# Audio_Power_Supply.net
KiCad netlist of a schematic drawn in Altium Designer
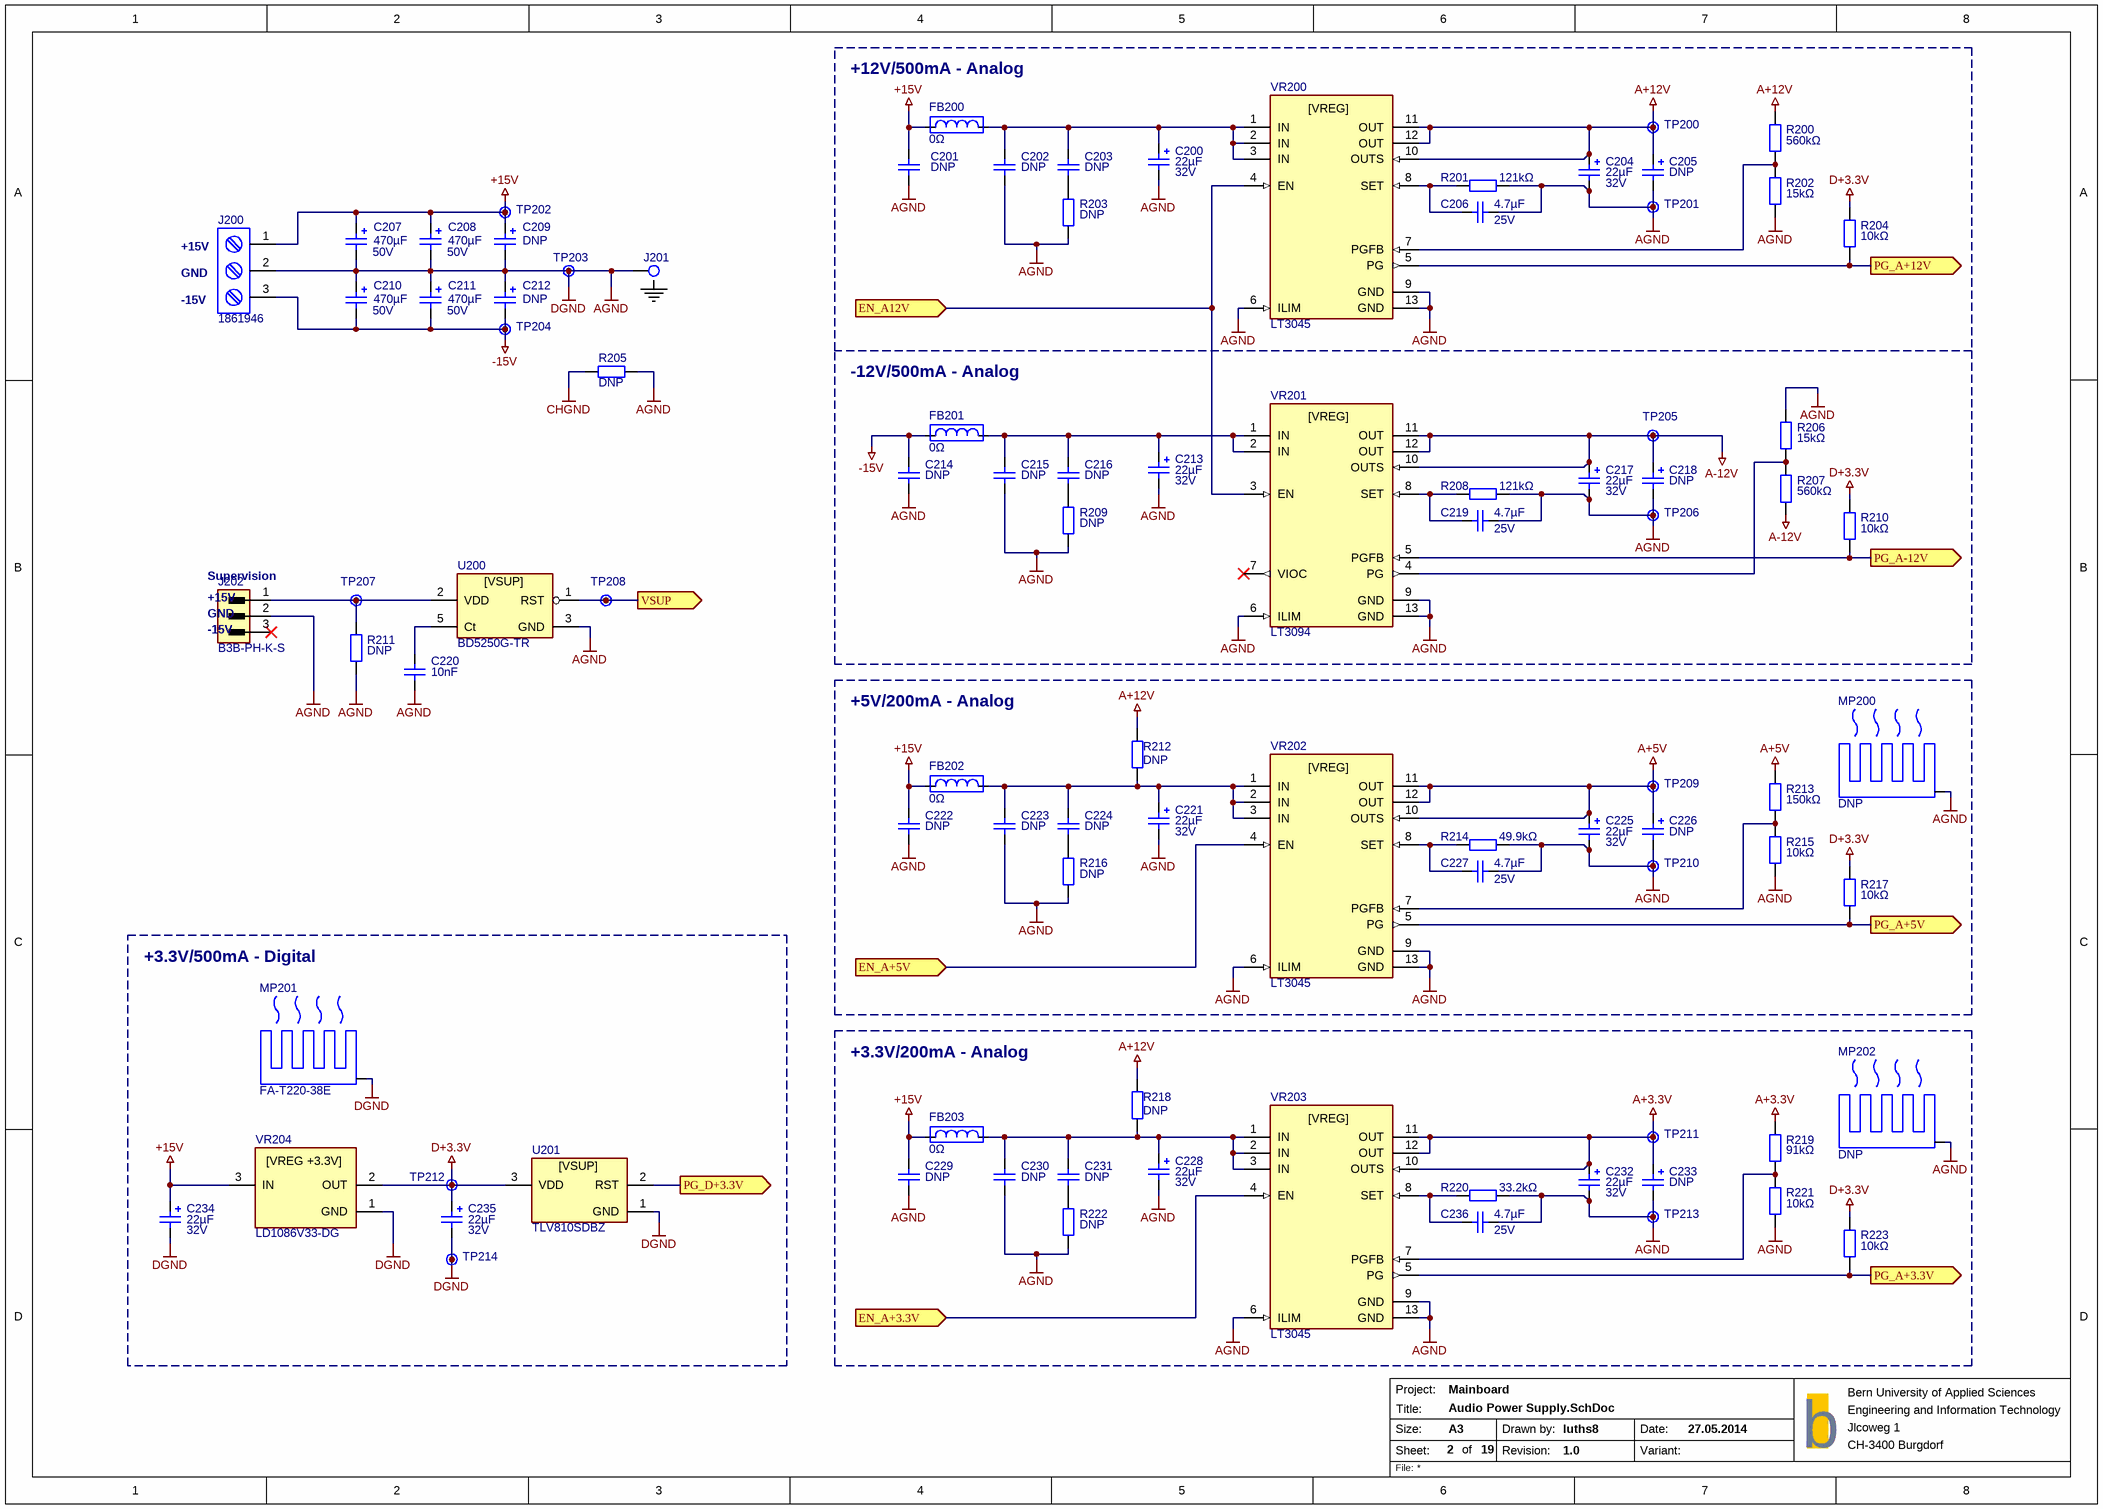
[diagram p0: Audio Power Supply.SchDoc]

(export (version "E")
  (design (tool "Eeschema 10.0.6"))
  (components
    (comp (ref "C200")
      (value "22µF")
      (footprint "CAP-6.3-5.5-2.5")
      (description "Elektrolytic Capacitor")
      (fields (field (name "VOLTAGE") "32V") (field (name "MANUFACTURER PART NO.") "32SEPF22M"))
      (libsource (lib "Audio-Streamer") (part "Capacitor Electrolytic"))
    )
    (comp (ref "C201")
      (value "DNP")
      (footprint "SMD0805CAP")
      (description "Ceramic Capacitor")
      (fields (field (name "VOLTAGE") "25V"))
      (libsource (lib "Audio-Streamer") (part "Capacitor Ceramic"))
    )
    (comp (ref "C202")
      (value "DNP")
      (footprint "SMD0805CAP")
      (description "Ceramic Capacitor")
      (fields (field (name "VOLTAGE") "25V"))
      (libsource (lib "Audio-Streamer") (part "Capacitor Ceramic"))
    )
    (comp (ref "C203")
      (value "DNP")
      (footprint "SMD0805CAP")
      (description "Ceramic Capacitor")
      (fields (field (name "VOLTAGE") "25V"))
      (libsource (lib "Audio-Streamer") (part "Capacitor Ceramic"))
    )
    (comp (ref "C204")
      (value "22µF")
      (footprint "CAP-6.3-5.5-2.5")
      (description "Elektrolytic Capacitor")
      (fields (field (name "VOLTAGE") "32V") (field (name "MANUFACTURER PART NO.") "32SEPF22M"))
      (libsource (lib "Audio-Streamer") (part "Capacitor Electrolytic"))
    )
    (comp (ref "C205")
      (value "DNP")
      (footprint "CAP-6.3-5.5-2.5")
      (description "Elektrolytic Capacitor")
      (fields (field (name "VOLTAGE") "32V") (field (name "MANUFACTURER PART NO.") "32SEPF22M"))
      (libsource (lib "Audio-Streamer") (part "Capacitor Electrolytic"))
    )
    (comp (ref "C206")
      (value "4.7µF")
      (footprint "SMD1206CAP")
      (description "Ceramic Capacitor")
      (fields (field (name "VOLTAGE") "25V"))
      (libsource (lib "Audio-Streamer") (part "Capacitor Ceramic"))
    )
    (comp (ref "C207")
      (value "470µF")
      (footprint "CAP-12.5-20-5")
      (description "Elektrolytic Capacitor")
      (fields (field (name "VOLTAGE") "50V") (field (name "MANUFACTURER PART NO.") "EEU-FR1H471"))
      (libsource (lib "Audio-Streamer") (part "Capacitor Electrolytic"))
    )
    (comp (ref "C208")
      (value "470µF")
      (footprint "CAP-12.5-20-5")
      (description "Elektrolytic Capacitor")
      (fields (field (name "VOLTAGE") "50V") (field (name "MANUFACTURER PART NO.") "EEU-FR1H471"))
      (libsource (lib "Audio-Streamer") (part "Capacitor Electrolytic"))
    )
    (comp (ref "C209")
      (value "DNP")
      (footprint "CAP-12.5-20-5")
      (description "Elektrolytic Capacitor")
      (fields (field (name "VOLTAGE") "50V") (field (name "MANUFACTURER PART NO.") "EEU-FR1H471"))
      (libsource (lib "Audio-Streamer") (part "Capacitor Electrolytic"))
    )
    (comp (ref "C210")
      (value "470µF")
      (footprint "CAP-12.5-20-5")
      (description "Elektrolytic Capacitor")
      (fields (field (name "VOLTAGE") "50V") (field (name "MANUFACTURER PART NO.") "EEU-FR1H471"))
      (libsource (lib "Audio-Streamer") (part "Capacitor Electrolytic"))
    )
    (comp (ref "C211")
      (value "470µF")
      (footprint "CAP-12.5-20-5")
      (description "Elektrolytic Capacitor")
      (fields (field (name "VOLTAGE") "50V") (field (name "MANUFACTURER PART NO.") "EEU-FR1H471"))
      (libsource (lib "Audio-Streamer") (part "Capacitor Electrolytic"))
    )
    (comp (ref "C212")
      (value "DNP")
      (footprint "CAP-12.5-20-5")
      (description "Elektrolytic Capacitor")
      (fields (field (name "VOLTAGE") "50V") (field (name "MANUFACTURER PART NO.") "EEU-FR1H471"))
      (libsource (lib "Audio-Streamer") (part "Capacitor Electrolytic"))
    )
    (comp (ref "C213")
      (value "22µF")
      (footprint "CAP-6.3-5.5-2.5")
      (description "Elektrolytic Capacitor")
      (fields (field (name "VOLTAGE") "32V") (field (name "MANUFACTURER PART NO.") "32SEPF22M"))
      (libsource (lib "Audio-Streamer") (part "Capacitor Electrolytic"))
    )
    (comp (ref "C214")
      (value "DNP")
      (footprint "SMD0805CAP")
      (description "Ceramic Capacitor")
      (fields (field (name "VOLTAGE") "25V"))
      (libsource (lib "Audio-Streamer") (part "Capacitor Ceramic"))
    )
    (comp (ref "C215")
      (value "DNP")
      (footprint "SMD0805CAP")
      (description "Ceramic Capacitor")
      (fields (field (name "VOLTAGE") "25V"))
      (libsource (lib "Audio-Streamer") (part "Capacitor Ceramic"))
    )
    (comp (ref "C216")
      (value "DNP")
      (footprint "SMD0805CAP")
      (description "Ceramic Capacitor")
      (fields (field (name "VOLTAGE") "25V"))
      (libsource (lib "Audio-Streamer") (part "Capacitor Ceramic"))
    )
    (comp (ref "C217")
      (value "22µF")
      (footprint "CAP-6.3-5.5-2.5")
      (description "Elektrolytic Capacitor")
      (fields (field (name "VOLTAGE") "32V") (field (name "MANUFACTURER PART NO.") "32SEPF22M"))
      (libsource (lib "Audio-Streamer") (part "Capacitor Electrolytic"))
    )
    (comp (ref "C218")
      (value "DNP")
      (footprint "CAP-6.3-5.5-2.5")
      (description "Elektrolytic Capacitor")
      (fields (field (name "VOLTAGE") "32V") (field (name "MANUFACTURER PART NO.") "32SEPF22M"))
      (libsource (lib "Audio-Streamer") (part "Capacitor Electrolytic"))
    )
    (comp (ref "C219")
      (value "4.7µF")
      (footprint "SMD1206CAP")
      (description "Ceramic Capacitor")
      (fields (field (name "VOLTAGE") "25V"))
      (libsource (lib "Audio-Streamer") (part "Capacitor Ceramic"))
    )
    (comp (ref "C220")
      (value "10nF")
      (footprint "SMD0603CAP")
      (description "Ceramic Capacitor")
      (fields (field (name "VOLTAGE") "25V"))
      (libsource (lib "Audio-Streamer") (part "Capacitor Ceramic"))
    )
    (comp (ref "C221")
      (value "22µF")
      (footprint "CAP-6.3-5.5-2.5")
      (description "Elektrolytic Capacitor")
      (fields (field (name "VOLTAGE") "32V") (field (name "MANUFACTURER PART NO.") "32SEPF22M"))
      (libsource (lib "Audio-Streamer") (part "Capacitor Electrolytic"))
    )
    (comp (ref "C222")
      (value "DNP")
      (footprint "SMD0805CAP")
      (description "Ceramic Capacitor")
      (fields (field (name "VOLTAGE") "25V"))
      (libsource (lib "Audio-Streamer") (part "Capacitor Ceramic"))
    )
    (comp (ref "C223")
      (value "DNP")
      (footprint "SMD0805CAP")
      (description "Ceramic Capacitor")
      (fields (field (name "VOLTAGE") "25V"))
      (libsource (lib "Audio-Streamer") (part "Capacitor Ceramic"))
    )
    (comp (ref "C224")
      (value "DNP")
      (footprint "SMD0805CAP")
      (description "Ceramic Capacitor")
      (fields (field (name "VOLTAGE") "25V"))
      (libsource (lib "Audio-Streamer") (part "Capacitor Ceramic"))
    )
    (comp (ref "C225")
      (value "22µF")
      (footprint "CAP-6.3-5.5-2.5")
      (description "Elektrolytic Capacitor")
      (fields (field (name "VOLTAGE") "32V") (field (name "MANUFACTURER PART NO.") "32SEPF22M"))
      (libsource (lib "Audio-Streamer") (part "Capacitor Electrolytic"))
    )
    (comp (ref "C226")
      (value "DNP")
      (footprint "CAP-6.3-5.5-2.5")
      (description "Elektrolytic Capacitor")
      (fields (field (name "VOLTAGE") "32V") (field (name "MANUFACTURER PART NO.") "32SEPF22M"))
      (libsource (lib "Audio-Streamer") (part "Capacitor Electrolytic"))
    )
    (comp (ref "C227")
      (value "4.7µF")
      (footprint "SMD1206CAP")
      (description "Ceramic Capacitor")
      (fields (field (name "VOLTAGE") "25V"))
      (libsource (lib "Audio-Streamer") (part "Capacitor Ceramic"))
    )
    (comp (ref "C228")
      (value "22µF")
      (footprint "CAP-6.3-5.5-2.5")
      (description "Elektrolytic Capacitor")
      (fields (field (name "VOLTAGE") "32V") (field (name "MANUFACTURER PART NO.") "32SEPF22M"))
      (libsource (lib "Audio-Streamer") (part "Capacitor Electrolytic"))
    )
    (comp (ref "C229")
      (value "DNP")
      (footprint "SMD0805CAP")
      (description "Ceramic Capacitor")
      (fields (field (name "VOLTAGE") "25V"))
      (libsource (lib "Audio-Streamer") (part "Capacitor Ceramic"))
    )
    (comp (ref "C230")
      (value "DNP")
      (footprint "SMD0805CAP")
      (description "Ceramic Capacitor")
      (fields (field (name "VOLTAGE") "25V"))
      (libsource (lib "Audio-Streamer") (part "Capacitor Ceramic"))
    )
    (comp (ref "C231")
      (value "DNP")
      (footprint "SMD0805CAP")
      (description "Ceramic Capacitor")
      (fields (field (name "VOLTAGE") "25V"))
      (libsource (lib "Audio-Streamer") (part "Capacitor Ceramic"))
    )
    (comp (ref "C232")
      (value "22µF")
      (footprint "CAP-6.3-5.5-2.5")
      (description "Elektrolytic Capacitor")
      (fields (field (name "VOLTAGE") "32V") (field (name "MANUFACTURER PART NO.") "32SEPF22M"))
      (libsource (lib "Audio-Streamer") (part "Capacitor Electrolytic"))
    )
    (comp (ref "C233")
      (value "DNP")
      (footprint "CAP-6.3-5.5-2.5")
      (description "Elektrolytic Capacitor")
      (fields (field (name "VOLTAGE") "32V") (field (name "MANUFACTURER PART NO.") "32SEPF22M"))
      (libsource (lib "Audio-Streamer") (part "Capacitor Electrolytic"))
    )
    (comp (ref "C234")
      (value "22µF")
      (footprint "CAP-6.3-5.5-2.5")
      (description "Elektrolytic Capacitor")
      (fields (field (name "VOLTAGE") "32V") (field (name "MANUFACTURER PART NO.") "32SEPF22M"))
      (libsource (lib "Audio-Streamer") (part "Capacitor Electrolytic"))
    )
    (comp (ref "C235")
      (value "22µF")
      (footprint "CAP-6.3-5.5-2.5")
      (description "Elektrolytic Capacitor")
      (fields (field (name "VOLTAGE") "32V") (field (name "MANUFACTURER PART NO.") "32SEPF22M"))
      (libsource (lib "Audio-Streamer") (part "Capacitor Electrolytic"))
    )
    (comp (ref "C236")
      (value "4.7µF")
      (footprint "SMD1206CAP")
      (description "Ceramic Capacitor")
      (fields (field (name "VOLTAGE") "25V"))
      (libsource (lib "Audio-Streamer") (part "Capacitor Ceramic"))
    )
    (comp (ref "FB200")
      (value "0Ω")
      (footprint "SMD0603RES")
      (description "Ferrite Bead")
      (libsource (lib "Audio-Streamer") (part "Ferrite Bead"))
    )
    (comp (ref "FB201")
      (value "0Ω")
      (footprint "SMD0603RES")
      (description "Ferrite Bead")
      (libsource (lib "Audio-Streamer") (part "Ferrite Bead"))
    )
    (comp (ref "FB202")
      (value "0Ω")
      (footprint "SMD0603RES")
      (description "Ferrite Bead")
      (libsource (lib "Audio-Streamer") (part "Ferrite Bead"))
    )
    (comp (ref "FB203")
      (value "0Ω")
      (footprint "SMD0603RES")
      (description "Ferrite Bead")
      (libsource (lib "Audio-Streamer") (part "Ferrite Bead"))
    )
    (comp (ref "J200")
      (value "1861946")
      (footprint "1861946")
      (description "Screw Terminal, 3 Position")
      (libsource (lib "Audio-Streamer") (part "1861946"))
    )
    (comp (ref "J201")
      (value "Solder Pin")
      (footprint "SOLDER_PIN")
      (libsource (lib "Audio-Streamer") (part "Solder Pin"))
    )
    (comp (ref "J202")
      (value "B3B-PH-K-S")
      (footprint "B3B-PH-K-S")
      (description "Connector 3x1P")
      (libsource (lib "Audio-Streamer") (part "Connector 3x1P"))
    )
    (comp (ref "MP200")
      (value "DNP")
      (footprint "DA-T263-201E")
      (description "Heatsink")
      (fields (field (name "MANUFACTURER PART NO.") "DA-T263-201E"))
      (libsource (lib "Audio-Streamer") (part "Heatsink"))
    )
    (comp (ref "MP201")
      (value "FA-T220-38E")
      (footprint "FA-T220-38E")
      (description "Heatsink")
      (libsource (lib "Audio-Streamer") (part "Heatsink"))
    )
    (comp (ref "MP202")
      (value "DNP")
      (footprint "DA-T263-201E")
      (description "Heatsink")
      (fields (field (name "MANUFACTURER PART NO.") "DA-T263-201E"))
      (libsource (lib "Audio-Streamer") (part "Heatsink"))
    )
    (comp (ref "R200")
      (value "560kΩ")
      (footprint "SMD0603RES")
      (description "Resistor")
      (libsource (lib "Audio-Streamer") (part "Resistor"))
    )
    (comp (ref "R201")
      (value "121kΩ")
      (footprint "SMD0603RES")
      (description "Resistor")
      (libsource (lib "") (part "Resistor_1"))
    )
    (comp (ref "R202")
      (value "15kΩ")
      (footprint "SMD0603RES")
      (description "Resistor")
      (libsource (lib "Audio-Streamer") (part "Resistor"))
    )
    (comp (ref "R203")
      (value "DNP")
      (footprint "SMD0603RES")
      (description "Resistor")
      (libsource (lib "Audio-Streamer") (part "Resistor"))
    )
    (comp (ref "R204")
      (value "10kΩ")
      (footprint "SMD0603RES")
      (description "Resistor")
      (libsource (lib "Audio-Streamer") (part "Resistor"))
    )
    (comp (ref "R205")
      (value "DNP")
      (footprint "SMD0805RES")
      (description "Resistor")
      (libsource (lib "") (part "Resistor_3"))
    )
    (comp (ref "R206")
      (value "15kΩ")
      (footprint "SMD0603RES")
      (description "Resistor")
      (libsource (lib "") (part "Resistor_3"))
    )
    (comp (ref "R207")
      (value "560kΩ")
      (footprint "SMD0603RES")
      (description "Resistor")
      (libsource (lib "") (part "Resistor_3"))
    )
    (comp (ref "R208")
      (value "121kΩ")
      (footprint "SMD0603RES")
      (description "Resistor")
      (libsource (lib "") (part "Resistor_1"))
    )
    (comp (ref "R209")
      (value "DNP")
      (footprint "SMD0603RES")
      (description "Resistor")
      (libsource (lib "Audio-Streamer") (part "Resistor"))
    )
    (comp (ref "R210")
      (value "10kΩ")
      (footprint "SMD0603RES")
      (description "Resistor")
      (libsource (lib "Audio-Streamer") (part "Resistor"))
    )
    (comp (ref "R211")
      (value "DNP")
      (footprint "SMD0603RES")
      (description "Resistor")
      (libsource (lib "Audio-Streamer") (part "Resistor"))
    )
    (comp (ref "R212")
      (value "DNP")
      (footprint "SMD0603RES")
      (description "Resistor")
      (libsource (lib "") (part "Resistor_2"))
    )
    (comp (ref "R213")
      (value "150kΩ")
      (footprint "SMD0603RES")
      (description "Resistor")
      (libsource (lib "Audio-Streamer") (part "Resistor"))
    )
    (comp (ref "R214")
      (value "49.9kΩ")
      (footprint "SMD0603RES")
      (description "Resistor")
      (libsource (lib "") (part "Resistor_1"))
    )
    (comp (ref "R215")
      (value "10kΩ")
      (footprint "SMD0603RES")
      (description "Resistor")
      (libsource (lib "Audio-Streamer") (part "Resistor"))
    )
    (comp (ref "R216")
      (value "DNP")
      (footprint "SMD0603RES")
      (description "Resistor")
      (libsource (lib "Audio-Streamer") (part "Resistor"))
    )
    (comp (ref "R217")
      (value "10kΩ")
      (footprint "SMD0603RES")
      (description "Resistor")
      (libsource (lib "Audio-Streamer") (part "Resistor"))
    )
    (comp (ref "R218")
      (value "DNP")
      (footprint "SMD0603RES")
      (description "Resistor")
      (libsource (lib "") (part "Resistor_2"))
    )
    (comp (ref "R219")
      (value "91kΩ")
      (footprint "SMD0603RES")
      (description "Resistor")
      (libsource (lib "Audio-Streamer") (part "Resistor"))
    )
    (comp (ref "R220")
      (value "33.2kΩ")
      (footprint "SMD0603RES")
      (description "Resistor")
      (libsource (lib "") (part "Resistor_1"))
    )
    (comp (ref "R221")
      (value "10kΩ")
      (footprint "SMD0603RES")
      (description "Resistor")
      (libsource (lib "Audio-Streamer") (part "Resistor"))
    )
    (comp (ref "R222")
      (value "DNP")
      (footprint "SMD0603RES")
      (description "Resistor")
      (libsource (lib "Audio-Streamer") (part "Resistor"))
    )
    (comp (ref "R223")
      (value "10kΩ")
      (footprint "SMD0603RES")
      (description "Resistor")
      (libsource (lib "Audio-Streamer") (part "Resistor"))
    )
    (comp (ref "TP200")
      (value "Testpoint")
      (footprint "TP")
      (libsource (lib "Audio-Streamer") (part "Testpoint"))
    )
    (comp (ref "TP201")
      (value "Testpoint")
      (footprint "TP")
      (libsource (lib "Audio-Streamer") (part "Testpoint"))
    )
    (comp (ref "TP202")
      (value "Testpoint")
      (footprint "TP")
      (libsource (lib "Audio-Streamer") (part "Testpoint"))
    )
    (comp (ref "TP203")
      (value "Testpoint")
      (footprint "TP")
      (libsource (lib "Audio-Streamer") (part "Testpoint"))
    )
    (comp (ref "TP204")
      (value "Testpoint")
      (footprint "TP")
      (libsource (lib "Audio-Streamer") (part "Testpoint"))
    )
    (comp (ref "TP205")
      (value "Testpoint")
      (footprint "TP")
      (libsource (lib "Audio-Streamer") (part "Testpoint"))
    )
    (comp (ref "TP206")
      (value "Testpoint")
      (footprint "TP")
      (libsource (lib "Audio-Streamer") (part "Testpoint"))
    )
    (comp (ref "TP207")
      (value "Testpoint")
      (footprint "TP")
      (libsource (lib "Audio-Streamer") (part "Testpoint"))
    )
    (comp (ref "TP208")
      (value "Testpoint")
      (footprint "TP")
      (libsource (lib "Audio-Streamer") (part "Testpoint"))
    )
    (comp (ref "TP209")
      (value "Testpoint")
      (footprint "TP")
      (libsource (lib "Audio-Streamer") (part "Testpoint"))
    )
    (comp (ref "TP210")
      (value "Testpoint")
      (footprint "TP")
      (libsource (lib "Audio-Streamer") (part "Testpoint"))
    )
    (comp (ref "TP211")
      (value "Testpoint")
      (footprint "TP")
      (libsource (lib "Audio-Streamer") (part "Testpoint"))
    )
    (comp (ref "TP212")
      (value "Testpoint")
      (footprint "TP")
      (libsource (lib "Audio-Streamer") (part "Testpoint"))
    )
    (comp (ref "TP213")
      (value "Testpoint")
      (footprint "TP")
      (libsource (lib "Audio-Streamer") (part "Testpoint"))
    )
    (comp (ref "TP214")
      (value "Testpoint")
      (footprint "TP")
      (libsource (lib "Audio-Streamer") (part "Testpoint"))
    )
    (comp (ref "U200")
      (value "BD5250G-TR")
      (footprint "SOT-23-5")
      (description "Voltage Supervisor, Threshold 5V")
      (libsource (lib "Audio-Streamer") (part "Voltage Supervisor 5V"))
    )
    (comp (ref "U201")
      (value "TLV810SDBZ")
      (footprint "SOT-23")
      (description "Voltage Supervisor, Threshold 2.94V")
      (fields (field (name "MANUFACTURER PART NO.") "TLV810SDBZR"))
      (libsource (lib "Audio-Streamer") (part "Voltage Supervisor"))
    )
    (comp (ref "VR200")
      (value "LT3045")
      (footprint "MSOP12")
      (description "Linear Regulator, positive Rail, Low Noise, High PSRR")
      (fields (field (name "MANUFACTURER PART NO.") "LT3045EMSE#PBF"))
      (libsource (lib "Audio-Streamer") (part "LT3045"))
    )
    (comp (ref "VR201")
      (value "LT3094")
      (footprint "MSOP12")
      (description "Linear Regulator, negative Rail Low Noise, High PSRR")
      (fields (field (name "MANUFACTURER PART NO.") "LT3094EMSE#PBF"))
      (libsource (lib "Audio-Streamer") (part "LT3094"))
    )
    (comp (ref "VR202")
      (value "LT3045")
      (footprint "MSOP12")
      (description "Linear Regulator, positive Rail, Low Noise, High PSRR")
      (fields (field (name "MANUFACTURER PART NO.") "LT3045EMSE#PBF"))
      (libsource (lib "Audio-Streamer") (part "LT3045"))
    )
    (comp (ref "VR203")
      (value "LT3045")
      (footprint "MSOP12")
      (description "Linear Regulator, positive Rail, Low Noise, High PSRR")
      (fields (field (name "MANUFACTURER PART NO.") "LT3045EMSE#PBF"))
      (libsource (lib "Audio-Streamer") (part "LT3045"))
    )
    (comp (ref "VR204")
      (value "LD1086V33-DG")
      (footprint "TO220-3")
      (description "Linear Voltage Regulator, positive Rail")
      (libsource (lib "Audio-Streamer") (part "LD1086V33-DG"))
    )
  )
  (nets
    (net (code "1") (name "+15V") (class "Default")
      (node (ref "C201") (pin "2") (pinfunction "q_2") (pintype "passive"))
      (node (ref "C207") (pin "P") (pinfunction "P_P") (pintype "passive"))
      (node (ref "C208") (pin "P") (pinfunction "P_P") (pintype "passive"))
      (node (ref "C209") (pin "P") (pinfunction "P_P") (pintype "passive"))
      (node (ref "C222") (pin "2") (pinfunction "q_2") (pintype "passive"))
      (node (ref "C229") (pin "2") (pinfunction "q_2") (pintype "passive"))
      (node (ref "C234") (pin "P") (pinfunction "P_P") (pintype "passive"))
      (node (ref "FB200") (pin "1") (pinfunction "1_1") (pintype "passive"))
      (node (ref "FB202") (pin "1") (pinfunction "1_1") (pintype "passive"))
      (node (ref "FB203") (pin "1") (pinfunction "1_1") (pintype "passive"))
      (node (ref "J200") (pin "1") (pinfunction "1_1") (pintype "passive"))
      (node (ref "TP202") (pin "1") (pinfunction "1_1") (pintype "passive"))
      (node (ref "VR204") (pin "3") (pinfunction "IN_3") (pintype "power_in"))
    )
    (net (code "2") (name "-15V") (class "Default")
      (node (ref "C210") (pin "M") (pinfunction "q_M") (pintype "passive"))
      (node (ref "C211") (pin "M") (pinfunction "q_M") (pintype "passive"))
      (node (ref "C212") (pin "M") (pinfunction "q_M") (pintype "passive"))
      (node (ref "C214") (pin "2") (pinfunction "q_2") (pintype "passive"))
      (node (ref "FB201") (pin "1") (pinfunction "1_1") (pintype "passive"))
      (node (ref "J200") (pin "3") (pinfunction "3_3") (pintype "passive"))
      (node (ref "TP204") (pin "1") (pinfunction "1_1") (pintype "passive"))
    )
    (net (code "3") (name "/EN_A+3.3V") (class "Default")
      (node (ref "VR203") (pin "4") (pinfunction "EN_4") (pintype "input"))
    )
    (net (code "4") (name "/EN_A+5V") (class "Default")
      (node (ref "VR202") (pin "4") (pinfunction "EN_4") (pintype "input"))
    )
    (net (code "5") (name "/EN_A12V") (class "Default")
      (node (ref "VR200") (pin "4") (pinfunction "EN_4") (pintype "input"))
      (node (ref "VR201") (pin "3") (pinfunction "EN_3") (pintype "input"))
    )
    (net (code "6") (name "/PG_A+3.3V") (class "Default")
      (node (ref "R223") (pin "1") (pinfunction "1_1") (pintype "passive"))
      (node (ref "VR203") (pin "5") (pinfunction "PG_5") (pintype "output"))
    )
    (net (code "7") (name "/PG_A+5V") (class "Default")
      (node (ref "R217") (pin "1") (pinfunction "1_1") (pintype "passive"))
      (node (ref "VR202") (pin "5") (pinfunction "PG_5") (pintype "output"))
    )
    (net (code "8") (name "/PG_A+12V") (class "Default")
      (node (ref "R204") (pin "1") (pinfunction "1_1") (pintype "passive"))
      (node (ref "VR200") (pin "5") (pinfunction "PG_5") (pintype "output"))
    )
    (net (code "9") (name "/PG_A-12V") (class "Default")
      (node (ref "R210") (pin "1") (pinfunction "1_1") (pintype "passive"))
      (node (ref "VR201") (pin "5") (pinfunction "PGFB_5") (pintype "input"))
    )
    (net (code "10") (name "/PG_D+3.3V") (class "Default")
      (node (ref "U201") (pin "2") (pinfunction "RST_2") (pintype "passive"))
    )
    (net (code "11") (name "/VSUP") (class "Default")
      (node (ref "TP208") (pin "1") (pinfunction "1_1") (pintype "passive"))
      (node (ref "U200") (pin "1") (pinfunction "RST_1") (pintype "open_collector"))
    )
    (net (code "12") (name "A+3.3V") (class "Default")
      (node (ref "C232") (pin "P") (pinfunction "P_P") (pintype "passive"))
      (node (ref "C233") (pin "P") (pinfunction "P_P") (pintype "passive"))
      (node (ref "R219") (pin "2") (pinfunction "2_2") (pintype "passive"))
      (node (ref "TP211") (pin "1") (pinfunction "1_1") (pintype "passive"))
      (node (ref "VR203") (pin "10") (pinfunction "OUTS_10") (pintype "input"))
      (node (ref "VR203") (pin "11") (pinfunction "OUT_11") (pintype "power_in"))
      (node (ref "VR203") (pin "12") (pinfunction "OUT_12") (pintype "power_in"))
    )
    (net (code "13") (name "A+5V") (class "Default")
      (node (ref "C225") (pin "P") (pinfunction "P_P") (pintype "passive"))
      (node (ref "C226") (pin "P") (pinfunction "P_P") (pintype "passive"))
      (node (ref "R213") (pin "2") (pinfunction "2_2") (pintype "passive"))
      (node (ref "TP209") (pin "1") (pinfunction "1_1") (pintype "passive"))
      (node (ref "VR202") (pin "10") (pinfunction "OUTS_10") (pintype "input"))
      (node (ref "VR202") (pin "11") (pinfunction "OUT_11") (pintype "power_in"))
      (node (ref "VR202") (pin "12") (pinfunction "OUT_12") (pintype "power_in"))
    )
    (net (code "14") (name "A+12V") (class "Default")
      (node (ref "C204") (pin "P") (pinfunction "P_P") (pintype "passive"))
      (node (ref "C205") (pin "P") (pinfunction "P_P") (pintype "passive"))
      (node (ref "R200") (pin "2") (pinfunction "2_2") (pintype "passive"))
      (node (ref "R212") (pin "1") (pinfunction "1_1") (pintype "passive"))
      (node (ref "R218") (pin "1") (pinfunction "1_1") (pintype "passive"))
      (node (ref "TP200") (pin "1") (pinfunction "1_1") (pintype "passive"))
      (node (ref "VR200") (pin "10") (pinfunction "OUTS_10") (pintype "input"))
      (node (ref "VR200") (pin "11") (pinfunction "OUT_11") (pintype "power_in"))
      (node (ref "VR200") (pin "12") (pinfunction "OUT_12") (pintype "power_in"))
    )
    (net (code "15") (name "A-12V") (class "Default")
      (node (ref "C217") (pin "P") (pinfunction "P_P") (pintype "passive"))
      (node (ref "C218") (pin "P") (pinfunction "P_P") (pintype "passive"))
      (node (ref "R207") (pin "2") (pinfunction "2_2") (pintype "passive"))
      (node (ref "TP205") (pin "1") (pinfunction "1_1") (pintype "passive"))
      (node (ref "VR201") (pin "10") (pinfunction "OUTS_10") (pintype "input"))
      (node (ref "VR201") (pin "11") (pinfunction "OUT_11") (pintype "power_in"))
      (node (ref "VR201") (pin "12") (pinfunction "OUT_12") (pintype "power_in"))
    )
    (net (code "16") (name "AGND") (class "Default")
      (node (ref "C200") (pin "M") (pinfunction "q_M") (pintype "passive"))
      (node (ref "C201") (pin "1") (pinfunction "1_1") (pintype "passive"))
      (node (ref "C202") (pin "1") (pinfunction "1_1") (pintype "passive"))
      (node (ref "C204") (pin "M") (pinfunction "q_M") (pintype "passive"))
      (node (ref "C205") (pin "M") (pinfunction "q_M") (pintype "passive"))
      (node (ref "C206") (pin "2") (pinfunction "q_2") (pintype "passive"))
      (node (ref "C207") (pin "M") (pinfunction "q_M") (pintype "passive"))
      (node (ref "C208") (pin "M") (pinfunction "q_M") (pintype "passive"))
      (node (ref "C209") (pin "M") (pinfunction "q_M") (pintype "passive"))
      (node (ref "C210") (pin "P") (pinfunction "P_P") (pintype "passive"))
      (node (ref "C211") (pin "P") (pinfunction "P_P") (pintype "passive"))
      (node (ref "C212") (pin "P") (pinfunction "P_P") (pintype "passive"))
      (node (ref "C213") (pin "M") (pinfunction "q_M") (pintype "passive"))
      (node (ref "C214") (pin "1") (pinfunction "1_1") (pintype "passive"))
      (node (ref "C215") (pin "1") (pinfunction "1_1") (pintype "passive"))
      (node (ref "C217") (pin "M") (pinfunction "q_M") (pintype "passive"))
      (node (ref "C218") (pin "M") (pinfunction "q_M") (pintype "passive"))
      (node (ref "C219") (pin "2") (pinfunction "q_2") (pintype "passive"))
      (node (ref "C220") (pin "1") (pinfunction "1_1") (pintype "passive"))
      (node (ref "C221") (pin "M") (pinfunction "q_M") (pintype "passive"))
      (node (ref "C222") (pin "1") (pinfunction "1_1") (pintype "passive"))
      (node (ref "C223") (pin "1") (pinfunction "1_1") (pintype "passive"))
      (node (ref "C225") (pin "M") (pinfunction "q_M") (pintype "passive"))
      (node (ref "C226") (pin "M") (pinfunction "q_M") (pintype "passive"))
      (node (ref "C227") (pin "2") (pinfunction "q_2") (pintype "passive"))
      (node (ref "C228") (pin "M") (pinfunction "q_M") (pintype "passive"))
      (node (ref "C229") (pin "1") (pinfunction "1_1") (pintype "passive"))
      (node (ref "C230") (pin "1") (pinfunction "1_1") (pintype "passive"))
      (node (ref "C232") (pin "M") (pinfunction "q_M") (pintype "passive"))
      (node (ref "C233") (pin "M") (pinfunction "q_M") (pintype "passive"))
      (node (ref "C234") (pin "M") (pinfunction "q_M") (pintype "passive"))
      (node (ref "C235") (pin "M") (pinfunction "q_M") (pintype "passive"))
      (node (ref "C236") (pin "2") (pinfunction "q_2") (pintype "passive"))
      (node (ref "J200") (pin "2") (pinfunction "2_2") (pintype "passive"))
      (node (ref "J201") (pin "1") (pinfunction "1_1") (pintype "passive"))
      (node (ref "J202") (pin "2") (pinfunction "2_2") (pintype "passive"))
      (node (ref "MP200") (pin "0") (pinfunction "0_0") (pintype "passive"))
      (node (ref "MP201") (pin "0") (pinfunction "0_0") (pintype "passive"))
      (node (ref "MP202") (pin "0") (pinfunction "0_0") (pintype "passive"))
      (node (ref "R201") (pin "2") (pinfunction "2_2") (pintype "passive"))
      (node (ref "R202") (pin "1") (pinfunction "1_1") (pintype "passive"))
      (node (ref "R203") (pin "1") (pinfunction "1_1") (pintype "passive"))
      (node (ref "R205") (pin "1") (pinfunction "1_1") (pintype "passive"))
      (node (ref "R206") (pin "1") (pinfunction "1_1") (pintype "passive"))
      (node (ref "R208") (pin "2") (pinfunction "2_2") (pintype "passive"))
      (node (ref "R209") (pin "1") (pinfunction "1_1") (pintype "passive"))
      (node (ref "R211") (pin "1") (pinfunction "1_1") (pintype "passive"))
      (node (ref "R214") (pin "2") (pinfunction "2_2") (pintype "passive"))
      (node (ref "R215") (pin "1") (pinfunction "1_1") (pintype "passive"))
      (node (ref "R216") (pin "1") (pinfunction "1_1") (pintype "passive"))
      (node (ref "R220") (pin "2") (pinfunction "2_2") (pintype "passive"))
      (node (ref "R221") (pin "1") (pinfunction "1_1") (pintype "passive"))
      (node (ref "R222") (pin "1") (pinfunction "1_1") (pintype "passive"))
      (node (ref "TP201") (pin "1") (pinfunction "1_1") (pintype "passive"))
      (node (ref "TP203") (pin "1") (pinfunction "1_1") (pintype "passive"))
      (node (ref "TP206") (pin "1") (pinfunction "1_1") (pintype "passive"))
      (node (ref "TP210") (pin "1") (pinfunction "1_1") (pintype "passive"))
      (node (ref "TP213") (pin "1") (pinfunction "1_1") (pintype "passive"))
      (node (ref "TP214") (pin "1") (pinfunction "1_1") (pintype "passive"))
      (node (ref "U200") (pin "3") (pinfunction "GND_3") (pintype "passive"))
      (node (ref "U201") (pin "1") (pinfunction "GND_1") (pintype "passive"))
      (node (ref "VR200") (pin "13") (pinfunction "GND_13") (pintype "power_in"))
      (node (ref "VR200") (pin "6") (pinfunction "ILIM_6") (pintype "input"))
      (node (ref "VR200") (pin "9") (pinfunction "GND_9") (pintype "power_in"))
      (node (ref "VR201") (pin "13") (pinfunction "GND_13") (pintype "power_in"))
      (node (ref "VR201") (pin "6") (pinfunction "ILIM_6") (pintype "input"))
      (node (ref "VR201") (pin "9") (pinfunction "GND_9") (pintype "power_in"))
      (node (ref "VR202") (pin "13") (pinfunction "GND_13") (pintype "power_in"))
      (node (ref "VR202") (pin "6") (pinfunction "ILIM_6") (pintype "input"))
      (node (ref "VR202") (pin "9") (pinfunction "GND_9") (pintype "power_in"))
      (node (ref "VR203") (pin "13") (pinfunction "GND_13") (pintype "power_in"))
      (node (ref "VR203") (pin "6") (pinfunction "ILIM_6") (pintype "input"))
      (node (ref "VR203") (pin "9") (pinfunction "GND_9") (pintype "power_in"))
      (node (ref "VR204") (pin "1") (pinfunction "GND_1") (pintype "power_in"))
    )
    (net (code "17") (name "CHGND") (class "Default")
      (node (ref "R205") (pin "2") (pinfunction "2_2") (pintype "passive"))
    )
    (net (code "18") (name "D+3.3V") (class "Default")
      (node (ref "C235") (pin "P") (pinfunction "P_P") (pintype "passive"))
      (node (ref "R204") (pin "2") (pinfunction "2_2") (pintype "passive"))
      (node (ref "R210") (pin "2") (pinfunction "2_2") (pintype "passive"))
      (node (ref "R217") (pin "2") (pinfunction "2_2") (pintype "passive"))
      (node (ref "R223") (pin "2") (pinfunction "2_2") (pintype "passive"))
      (node (ref "TP212") (pin "1") (pinfunction "1_1") (pintype "passive"))
      (node (ref "U201") (pin "3") (pinfunction "VDD_3") (pintype "passive"))
      (node (ref "VR204") (pin "2") (pinfunction "OUT_2") (pintype "power_in"))
    )
    (net (code "19") (name "Net-(C202-q)") (class "Default")
      (node (ref "C200") (pin "P") (pinfunction "P_P") (pintype "passive"))
      (node (ref "C202") (pin "2") (pinfunction "q_2") (pintype "passive"))
      (node (ref "C203") (pin "2") (pinfunction "q_2") (pintype "passive"))
      (node (ref "FB200") (pin "2") (pinfunction "2_2") (pintype "passive"))
      (node (ref "VR200") (pin "1") (pinfunction "IN_1") (pintype "power_in"))
      (node (ref "VR200") (pin "2") (pinfunction "IN_2") (pintype "power_in"))
      (node (ref "VR200") (pin "3") (pinfunction "IN_3") (pintype "power_in"))
    )
    (net (code "20") (name "Net-(C203-Pad1)") (class "Default")
      (node (ref "C203") (pin "1") (pinfunction "1_1") (pintype "passive"))
      (node (ref "R203") (pin "2") (pinfunction "2_2") (pintype "passive"))
    )
    (net (code "21") (name "Net-(C215-q)") (class "Default")
      (node (ref "C213") (pin "P") (pinfunction "P_P") (pintype "passive"))
      (node (ref "C215") (pin "2") (pinfunction "q_2") (pintype "passive"))
      (node (ref "C216") (pin "2") (pinfunction "q_2") (pintype "passive"))
      (node (ref "FB201") (pin "2") (pinfunction "2_2") (pintype "passive"))
      (node (ref "VR201") (pin "1") (pinfunction "IN_1") (pintype "power_in"))
      (node (ref "VR201") (pin "2") (pinfunction "IN_2") (pintype "power_in"))
    )
    (net (code "22") (name "Net-(C216-Pad1)") (class "Default")
      (node (ref "C216") (pin "1") (pinfunction "1_1") (pintype "passive"))
      (node (ref "R209") (pin "2") (pinfunction "2_2") (pintype "passive"))
    )
    (net (code "23") (name "Net-(C220-q)") (class "Default")
      (node (ref "C220") (pin "2") (pinfunction "q_2") (pintype "passive"))
      (node (ref "U200") (pin "5") (pinfunction "Ct_5") (pintype "passive"))
    )
    (net (code "24") (name "Net-(C223-q)") (class "Default")
      (node (ref "C221") (pin "P") (pinfunction "P_P") (pintype "passive"))
      (node (ref "C223") (pin "2") (pinfunction "q_2") (pintype "passive"))
      (node (ref "C224") (pin "2") (pinfunction "q_2") (pintype "passive"))
      (node (ref "FB202") (pin "2") (pinfunction "2_2") (pintype "passive"))
      (node (ref "R212") (pin "2") (pinfunction "2_2") (pintype "passive"))
      (node (ref "VR202") (pin "1") (pinfunction "IN_1") (pintype "power_in"))
      (node (ref "VR202") (pin "2") (pinfunction "IN_2") (pintype "power_in"))
      (node (ref "VR202") (pin "3") (pinfunction "IN_3") (pintype "power_in"))
    )
    (net (code "25") (name "Net-(C224-Pad1)") (class "Default")
      (node (ref "C224") (pin "1") (pinfunction "1_1") (pintype "passive"))
      (node (ref "R216") (pin "2") (pinfunction "2_2") (pintype "passive"))
    )
    (net (code "26") (name "Net-(C230-q)") (class "Default")
      (node (ref "C228") (pin "P") (pinfunction "P_P") (pintype "passive"))
      (node (ref "C230") (pin "2") (pinfunction "q_2") (pintype "passive"))
      (node (ref "C231") (pin "2") (pinfunction "q_2") (pintype "passive"))
      (node (ref "FB203") (pin "2") (pinfunction "2_2") (pintype "passive"))
      (node (ref "R218") (pin "2") (pinfunction "2_2") (pintype "passive"))
      (node (ref "VR203") (pin "1") (pinfunction "IN_1") (pintype "power_in"))
      (node (ref "VR203") (pin "2") (pinfunction "IN_2") (pintype "power_in"))
      (node (ref "VR203") (pin "3") (pinfunction "IN_3") (pintype "power_in"))
    )
    (net (code "27") (name "Net-(C231-Pad1)") (class "Default")
      (node (ref "C231") (pin "1") (pinfunction "1_1") (pintype "passive"))
      (node (ref "R222") (pin "2") (pinfunction "2_2") (pintype "passive"))
    )
    (net (code "28") (name "Net-(U200-VDD)") (class "Default")
      (node (ref "J202") (pin "1") (pinfunction "1_1") (pintype "passive"))
      (node (ref "R211") (pin "2") (pinfunction "2_2") (pintype "passive"))
      (node (ref "TP207") (pin "1") (pinfunction "1_1") (pintype "passive"))
      (node (ref "U200") (pin "2") (pinfunction "VDD_2") (pintype "passive"))
    )
    (net (code "29") (name "Net-(VR200-PGFB)") (class "Default")
      (node (ref "R200") (pin "1") (pinfunction "1_1") (pintype "passive"))
      (node (ref "R202") (pin "2") (pinfunction "2_2") (pintype "passive"))
      (node (ref "VR200") (pin "7") (pinfunction "PGFB_7") (pintype "input"))
    )
    (net (code "30") (name "Net-(VR200-SET)") (class "Default")
      (node (ref "C206") (pin "1") (pinfunction "1_1") (pintype "passive"))
      (node (ref "R201") (pin "1") (pinfunction "1_1") (pintype "passive"))
      (node (ref "VR200") (pin "8") (pinfunction "SET_8") (pintype "input"))
    )
    (net (code "31") (name "Net-(VR201-PG)") (class "Default")
      (node (ref "R206") (pin "2") (pinfunction "2_2") (pintype "passive"))
      (node (ref "R207") (pin "1") (pinfunction "1_1") (pintype "passive"))
      (node (ref "VR201") (pin "4") (pinfunction "PG_4") (pintype "output"))
    )
    (net (code "32") (name "Net-(VR201-SET)") (class "Default")
      (node (ref "C219") (pin "1") (pinfunction "1_1") (pintype "passive"))
      (node (ref "R208") (pin "1") (pinfunction "1_1") (pintype "passive"))
      (node (ref "VR201") (pin "8") (pinfunction "SET_8") (pintype "input"))
    )
    (net (code "33") (name "Net-(VR202-PGFB)") (class "Default")
      (node (ref "R213") (pin "1") (pinfunction "1_1") (pintype "passive"))
      (node (ref "R215") (pin "2") (pinfunction "2_2") (pintype "passive"))
      (node (ref "VR202") (pin "7") (pinfunction "PGFB_7") (pintype "input"))
    )
    (net (code "34") (name "Net-(VR202-SET)") (class "Default")
      (node (ref "C227") (pin "1") (pinfunction "1_1") (pintype "passive"))
      (node (ref "R214") (pin "1") (pinfunction "1_1") (pintype "passive"))
      (node (ref "VR202") (pin "8") (pinfunction "SET_8") (pintype "input"))
    )
    (net (code "35") (name "Net-(VR203-PGFB)") (class "Default")
      (node (ref "R219") (pin "1") (pinfunction "1_1") (pintype "passive"))
      (node (ref "R221") (pin "2") (pinfunction "2_2") (pintype "passive"))
      (node (ref "VR203") (pin "7") (pinfunction "PGFB_7") (pintype "input"))
    )
    (net (code "36") (name "Net-(VR203-SET)") (class "Default")
      (node (ref "C236") (pin "1") (pinfunction "1_1") (pintype "passive"))
      (node (ref "R220") (pin "1") (pinfunction "1_1") (pintype "passive"))
      (node (ref "VR203") (pin "8") (pinfunction "SET_8") (pintype "input"))
    )
    (net (code "37") (name "unconnected-(J202-Pad3)") (class "Default")
      (node (ref "J202") (pin "3") (pinfunction "3_3") (pintype "passive+no_connect"))
    )
    (net (code "38") (name "unconnected-(VR201-VIOC-Pad7)") (class "Default")
      (node (ref "VR201") (pin "7") (pinfunction "VIOC_7") (pintype "output+no_connect"))
    )
  )
)
